# ClockCircuit.net
KiCad netlist of a schematic drawn in Altium Designer
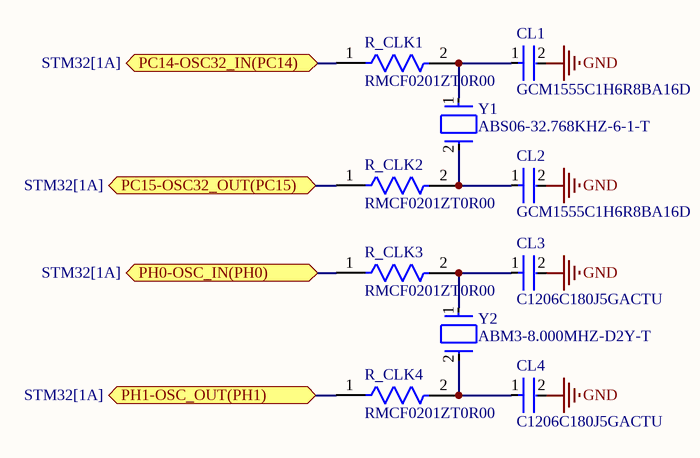
[diagram p0: ClockCircuit.SchDoc]

(export (version "E")
  (design (tool "Eeschema 10.0.6"))
  (components
    (comp (ref "CL1")
      (value "GCM1555C1H6R8BA16D")
      (footprint "FP-GCM155-0_05-MFG")
      (description "Ceramic Capacitor for Automotive 6.8pF ±0.1pF 50VDC C0G 0402 Paper T/R")
      (libsource (lib "Altium Content Vault") (part "02cd4be3c70576c341d710602a673aa"))
    )
    (comp (ref "CL2")
      (value "GCM1555C1H6R8BA16D")
      (footprint "FP-GCM155-0_05-MFG")
      (description "Ceramic Capacitor for Automotive 6.8pF ±0.1pF 50VDC C0G 0402 Paper T/R")
      (libsource (lib "Altium Content Vault") (part "02cd4be3c70576c341d710602a673aa"))
    )
    (comp (ref "CL3")
      (value "C1206C180J5GACTU")
      (footprint "FP-C1206C-EB-MFG")
      (description "1206 C 18pF Ceramic Multilayer Capacitor; 50 VDC; +125degC; C0G Dielec; +/-5%")
      (fields
        (field (name "TOLERANCE") "0.05")
        (field (name "OCTOPART") "https://octopart.com/c1206c180j5gactu-kemet-90945")
      )
      (libsource (lib "Altium Content Vault") (part "b4654b650e69147ec39a6b967a45e02"))
    )
    (comp (ref "CL4")
      (value "C1206C180J5GACTU")
      (footprint "FP-C1206C-EB-MFG")
      (description "1206 C 18pF Ceramic Multilayer Capacitor; 50 VDC; +125degC; C0G Dielec; +/-5%")
      (fields
        (field (name "TOLERANCE") "0.05")
        (field (name "OCTOPART") "https://octopart.com/c1206c180j5gactu-kemet-90945")
      )
      (libsource (lib "Altium Content Vault") (part "b4654b650e69147ec39a6b967a45e02"))
    )
    (comp (ref "R_CLK1")
      (value "RMCF0201ZT0R00")
      (footprint "FP-RMCF0201-IPC_C")
      (description "0Ω ±0 0.05W 0201 Thick Film Chip Resistor AEC-Q200 compliant")
      (libsource (lib "Altium Content Vault") (part "1029c3af85768c4190bb7ad29bc67b5"))
    )
    (comp (ref "R_CLK2")
      (value "RMCF0201ZT0R00")
      (footprint "FP-RMCF0201-IPC_C")
      (description "0Ω ±0 0.05W 0201 Thick Film Chip Resistor AEC-Q200 compliant")
      (libsource (lib "Altium Content Vault") (part "1029c3af85768c4190bb7ad29bc67b5"))
    )
    (comp (ref "R_CLK3")
      (value "RMCF0201ZT0R00")
      (footprint "FP-RMCF0201-IPC_C")
      (description "0Ω ±0 0.05W 0201 Thick Film Chip Resistor AEC-Q200 compliant")
      (libsource (lib "Altium Content Vault") (part "1029c3af85768c4190bb7ad29bc67b5"))
    )
    (comp (ref "R_CLK4")
      (value "RMCF0201ZT0R00")
      (footprint "FP-RMCF0201-IPC_C")
      (description "0Ω ±0 0.05W 0201 Thick Film Chip Resistor AEC-Q200 compliant")
      (libsource (lib "Altium Content Vault") (part "1029c3af85768c4190bb7ad29bc67b5"))
    )
    (comp (ref "Y1")
      (value "ABS06-32.768KHZ-6-1-T")
      (footprint "FP-ABS06-MFG")
      (description "Crystal 32.768kHz ±10ppm (Tol) 6pF FUND 90kΩ 2-Pin Mini-CSMD T/R")
      (libsource (lib "Altium Content Vault") (part "c23a69dc6c9e2f18f2079038eb95dd1"))
    )
    (comp (ref "Y2")
      (value "ABM3-8.000MHZ-D2Y-T")
      (footprint "FP-ABM3-MFG")
      (description "Crystal 8MHz ±20ppm 18pF SMD-2 5mm x 3.2mm")
      (fields (field (name "TOLERANCE") "20ppm"))
      (libsource (lib "Altium Content Vault") (part "c23a69dc6c9e2f18f2079038eb95dd1"))
    )
  )
  (nets
    (net (code "1") (name "/PC14-OSC32_IN(PC14)") (class "Default")
      (node (ref "R_CLK1") (pin "1") (pinfunction "1_1") (pintype "passive"))
    )
    (net (code "2") (name "/PC15-OSC32_OUT(PC15)") (class "Default")
      (node (ref "R_CLK2") (pin "1") (pinfunction "1_1") (pintype "passive"))
    )
    (net (code "3") (name "/PH0-OSC_IN(PH0)") (class "Default")
      (node (ref "R_CLK3") (pin "1") (pinfunction "1_1") (pintype "passive"))
    )
    (net (code "4") (name "/PH1-OSC_OUT(PH1)") (class "Default")
      (node (ref "R_CLK4") (pin "1") (pinfunction "1_1") (pintype "passive"))
    )
    (net (code "5") (name "GND") (class "Default")
      (node (ref "CL1") (pin "2") (pinfunction "2_2") (pintype "passive"))
      (node (ref "CL2") (pin "2") (pinfunction "2_2") (pintype "passive"))
      (node (ref "CL3") (pin "2") (pinfunction "2_2") (pintype "passive"))
      (node (ref "CL4") (pin "2") (pinfunction "2_2") (pintype "passive"))
    )
    (net (code "6") (name "Net-(CL1-Pad1)") (class "Default")
      (node (ref "CL1") (pin "1") (pinfunction "1_1") (pintype "passive"))
      (node (ref "R_CLK1") (pin "2") (pinfunction "2_2") (pintype "passive"))
      (node (ref "Y1") (pin "1") (pinfunction "1_1") (pintype "passive"))
    )
    (net (code "7") (name "Net-(CL2-Pad1)") (class "Default")
      (node (ref "CL2") (pin "1") (pinfunction "1_1") (pintype "passive"))
      (node (ref "R_CLK2") (pin "2") (pinfunction "2_2") (pintype "passive"))
      (node (ref "Y1") (pin "2") (pinfunction "2_2") (pintype "passive"))
    )
    (net (code "8") (name "Net-(CL3-Pad1)") (class "Default")
      (node (ref "CL3") (pin "1") (pinfunction "1_1") (pintype "passive"))
      (node (ref "R_CLK3") (pin "2") (pinfunction "2_2") (pintype "passive"))
      (node (ref "Y2") (pin "1") (pinfunction "1_1") (pintype "passive"))
    )
    (net (code "9") (name "Net-(CL4-Pad1)") (class "Default")
      (node (ref "CL4") (pin "1") (pinfunction "1_1") (pintype "passive"))
      (node (ref "R_CLK4") (pin "2") (pinfunction "2_2") (pintype "passive"))
      (node (ref "Y2") (pin "2") (pinfunction "2_2") (pintype "passive"))
    )
  )
)
